# MCU.net
KiCad netlist of a schematic drawn in Altium Designer
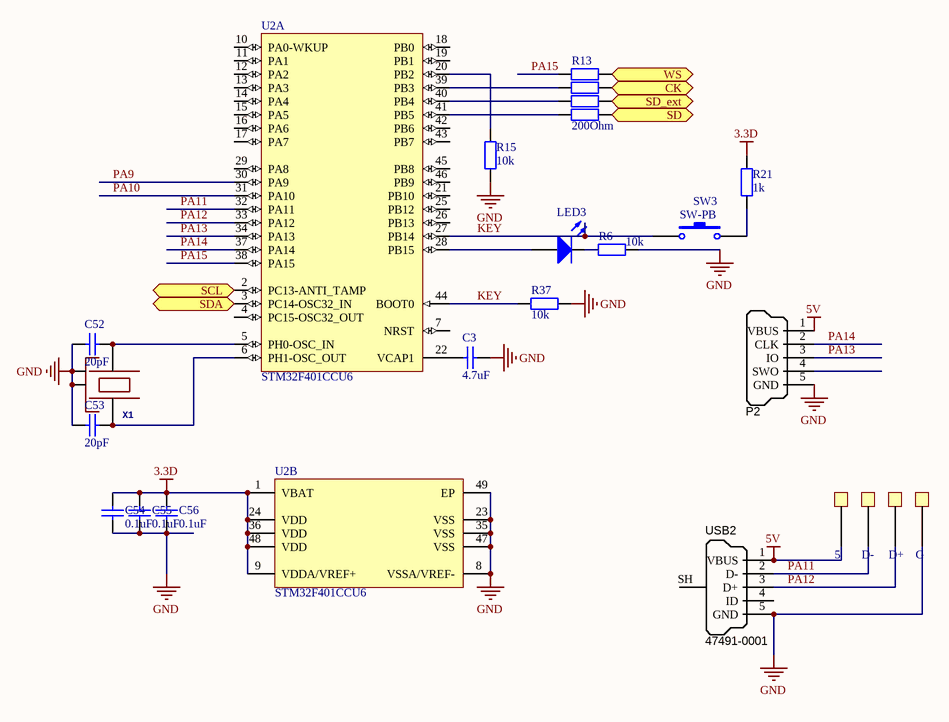
[diagram p0: MCU.SchDoc]

(export (version "E")
  (design (tool "Eeschema 10.0.6"))
  (components
    (comp (ref "5") (value "TestPad") (footprint "TestPad") (libsource (lib "sch") (part "TestPad")))
    (comp (ref "C3")
      (value "4.7uF")
      (footprint "0603L")
      (description "Capacitor")
      (fields (field (name "Comment") "Cap") (field (name "PUBLISHER") "Altium Limited"))
      (libsource (lib "RTC6705") (part "Cap"))
    )
    (comp (ref "C52")
      (value "20pF")
      (footprint "0402")
      (description "Capacitor")
      (fields (field (name "Comment") "Cap") (field (name "PUBLISHER") "Altium Limited"))
      (libsource (lib "RTC6705") (part "Cap"))
    )
    (comp (ref "C53")
      (value "20pF")
      (footprint "0402")
      (description "Capacitor")
      (fields (field (name "Comment") "Cap") (field (name "PUBLISHER") "Altium Limited"))
      (libsource (lib "RTC6705") (part "Cap"))
    )
    (comp (ref "C54")
      (value "0.1uF")
      (footprint "0402")
      (description "Capacitor")
      (fields (field (name "Comment") "Cap") (field (name "PUBLISHER") "Altium Limited"))
      (libsource (lib "RTC6705") (part "Cap"))
    )
    (comp (ref "C55")
      (value "0.1uF")
      (footprint "0402")
      (description "Capacitor")
      (fields (field (name "Comment") "Cap") (field (name "PUBLISHER") "Altium Limited"))
      (libsource (lib "RTC6705") (part "Cap"))
    )
    (comp (ref "C56")
      (value "0.1uF")
      (footprint "0402")
      (description "Capacitor")
      (fields (field (name "Comment") "Cap") (field (name "PUBLISHER") "Altium Limited"))
      (libsource (lib "RTC6705") (part "Cap"))
    )
    (comp (ref "D+") (value "TestPad") (footprint "TestPad") (libsource (lib "sch") (part "TestPad")))
    (comp (ref "D-") (value "TestPad") (footprint "TestPad") (libsource (lib "sch") (part "TestPad")))
    (comp (ref "G") (value "TestPad") (footprint "TestPad") (libsource (lib "sch") (part "TestPad")))
    (comp (ref "LED3")
      (value "LED0")
      (footprint "0603")
      (description "Typical INFRARED GaAs LED")
      (fields (field (name "PUBLISHER") "Altium Limited"))
      (libsource (lib "Miscellaneous Devices") (part "LED0"))
    )
    (comp (ref "P2")
      (value "SWD_MicroUSB")
      (footprint "MICRO-YZX")
      (description "Connector SMD USB Micro Type B middle mount")
      (libsource (lib "sch") (part "SWD_MicroUSB"))
    )
    (comp (ref "R6")
      (value "10k")
      (footprint "0402")
      (description "Resistor")
      (fields (field (name "PUBLISHER") "Altium Limited"))
      (libsource (lib "") (part "Res2_2"))
    )
    (comp (ref "R13")
      (value "200Ohm")
      (footprint "0402X4")
      (description "Resistor")
      (fields (field (name "Comment") "Res*4") (field (name "PUBLISHER") "Altium Limited"))
      (libsource (lib "sch") (part "Res*4"))
    )
    (comp (ref "R15")
      (value "10k")
      (footprint "0402")
      (description "Resistor")
      (fields (field (name "PUBLISHER") "Altium Limited"))
      (libsource (lib "") (part "Res2_1"))
    )
    (comp (ref "R21")
      (value "1k")
      (footprint "0402")
      (description "Resistor")
      (fields (field (name "PUBLISHER") "Altium Limited"))
      (libsource (lib "Miscellaneous Devices") (part "Res2"))
    )
    (comp (ref "R37")
      (value "10k")
      (footprint "0402")
      (description "Resistor")
      (fields (field (name "Comment") "Res2") (field (name "PUBLISHER") "Altium Limited"))
      (libsource (lib "RTC6705") (part "Res2"))
    )
    (comp (ref "SW3")
      (value "SW-PB")
      (footprint "SW3x4")
      (description "Switch")
      (fields (field (name "PUBLISHER") "Altium Limited"))
      (libsource (lib "Miscellaneous Devices") (part "SW-PB"))
    )
    (comp (ref "U2")
      (value "STM32F401CCU6")
      (footprint "STM-UFQFPN48_N")
      (fields (field (name "MANUFACTURER") "STMicroelectronics"))
      (libsource (lib "STMicroelectronics STM32 F4") (part "STM32F401CCU6"))
    )
    (comp (ref "USB2")
      (value "USB Micro Type B")
      (footprint "MICRO-YZX")
      (description "Connector SMD USB Micro Type B middle mount")
      (fields (field (name "MANUFACTURER PART NUMBER 1") "47491-0001"))
      (libsource (lib "PBL - Connectors") (part "USB_Micro_TypeB"))
    )
    (comp (ref "X1")
      (value "24.000 KHz 3.2x2.5mm 8-10pf")
      (footprint "OSCILLATOR-2.5x2.0")
      (description "Crystal Oscillator in 3.2x2.5 SMD")
      (libsource (lib "pixhawk2") (part "OSCILLATOR-3.2X2.5"))
    )
  )
  (nets
    (net (code "1") (name "/CK") (class "Default")
      (node (ref "R13") (pin "2") (pinfunction "2_2") (pintype "passive"))
    )
    (net (code "2") (name "/KEY") (class "Default")
      (node (ref "R37") (pin "1") (pinfunction "1_1") (pintype "passive"))
      (node (ref "SW3") (pin "1") (pinfunction "1_1") (pintype "passive"))
      (node (ref "U2") (pin "27") (pinfunction "PB14_27") (pintype "bidirectional"))
      (node (ref "U2") (pin "44") (pinfunction "BOOT0_44") (pintype "input"))
    )
    (net (code "3") (name "/PA9") (class "Default")
      (node (ref "U2") (pin "30") (pinfunction "PA9_30") (pintype "bidirectional"))
    )
    (net (code "4") (name "/PA10") (class "Default")
      (node (ref "U2") (pin "31") (pinfunction "PA10_31") (pintype "bidirectional"))
    )
    (net (code "5") (name "/PA11") (class "Default")
      (node (ref "D-") (pin "1") (pinfunction "3_1") (pintype "passive"))
      (node (ref "U2") (pin "32") (pinfunction "PA11_32") (pintype "bidirectional"))
      (node (ref "USB2") (pin "2") (pinfunction "D-_2") (pintype "passive"))
    )
    (net (code "6") (name "/PA12") (class "Default")
      (node (ref "D+") (pin "1") (pinfunction "3_1") (pintype "passive"))
      (node (ref "U2") (pin "33") (pinfunction "PA12_33") (pintype "bidirectional"))
      (node (ref "USB2") (pin "3") (pinfunction "D+_3") (pintype "passive"))
    )
    (net (code "7") (name "/PA13") (class "Default")
      (node (ref "P2") (pin "3") (pinfunction "IO_3") (pintype "passive"))
      (node (ref "U2") (pin "34") (pinfunction "PA13_34") (pintype "bidirectional"))
    )
    (net (code "8") (name "/PA14") (class "Default")
      (node (ref "P2") (pin "2") (pinfunction "CLK_2") (pintype "passive"))
      (node (ref "U2") (pin "37") (pinfunction "PA14_37") (pintype "bidirectional"))
    )
    (net (code "9") (name "/PA15") (class "Default")
      (node (ref "R13") (pin "8") (pinfunction "8_8") (pintype "passive"))
      (node (ref "U2") (pin "38") (pinfunction "PA15_38") (pintype "bidirectional"))
    )
    (net (code "10") (name "/SCL") (class "Default")
      (node (ref "U2") (pin "2") (pinfunction "PC13-ANTI_TAMP_2") (pintype "bidirectional"))
    )
    (net (code "11") (name "/SD") (class "Default")
      (node (ref "R13") (pin "4") (pinfunction "4_4") (pintype "passive"))
    )
    (net (code "12") (name "/SDA") (class "Default")
      (node (ref "U2") (pin "3") (pinfunction "PC14-OSC32_IN_3") (pintype "bidirectional"))
    )
    (net (code "13") (name "/SD_ext") (class "Default")
      (node (ref "R13") (pin "3") (pinfunction "3_3") (pintype "passive"))
    )
    (net (code "14") (name "/WS") (class "Default")
      (node (ref "R13") (pin "1") (pinfunction "1_1") (pintype "passive"))
    )
    (net (code "15") (name "3.3D") (class "Default")
      (node (ref "C54") (pin "2") (pinfunction "2_2") (pintype "passive"))
      (node (ref "C55") (pin "2") (pinfunction "2_2") (pintype "passive"))
      (node (ref "C56") (pin "2") (pinfunction "2_2") (pintype "passive"))
      (node (ref "R21") (pin "2") (pinfunction "2_2") (pintype "passive"))
      (node (ref "U2") (pin "1") (pinfunction "VBAT_1") (pintype "power_in"))
      (node (ref "U2") (pin "24") (pinfunction "VDD_24") (pintype "power_in"))
      (node (ref "U2") (pin "36") (pinfunction "VDD_36") (pintype "power_in"))
      (node (ref "U2") (pin "48") (pinfunction "VDD_48") (pintype "power_in"))
      (node (ref "U2") (pin "9") (pinfunction "VDDA/VREF+_9") (pintype "power_in"))
    )
    (net (code "16") (name "5V") (class "Default")
      (node (ref "5") (pin "1") (pinfunction "3_1") (pintype "passive"))
      (node (ref "P2") (pin "1") (pinfunction "VBUS_1") (pintype "passive"))
      (node (ref "USB2") (pin "1") (pinfunction "VBUS_1") (pintype "passive"))
    )
    (net (code "17") (name "GND") (class "Default")
      (node (ref "C3") (pin "1") (pinfunction "1_1") (pintype "passive"))
      (node (ref "C52") (pin "1") (pinfunction "1_1") (pintype "passive"))
      (node (ref "C53") (pin "1") (pinfunction "1_1") (pintype "passive"))
      (node (ref "C54") (pin "1") (pinfunction "1_1") (pintype "passive"))
      (node (ref "C55") (pin "1") (pinfunction "1_1") (pintype "passive"))
      (node (ref "C56") (pin "1") (pinfunction "1_1") (pintype "passive"))
      (node (ref "G") (pin "1") (pinfunction "3_1") (pintype "passive"))
      (node (ref "P2") (pin "5") (pinfunction "GND_5") (pintype "passive"))
      (node (ref "R15") (pin "2") (pinfunction "2_2") (pintype "passive"))
      (node (ref "R37") (pin "2") (pinfunction "2_2") (pintype "passive"))
      (node (ref "R6") (pin "2") (pinfunction "2_2") (pintype "passive"))
      (node (ref "U2") (pin "23") (pinfunction "VSS_23") (pintype "power_in"))
      (node (ref "U2") (pin "35") (pinfunction "VSS_35") (pintype "power_in"))
      (node (ref "U2") (pin "47") (pinfunction "VSS_47") (pintype "power_in"))
      (node (ref "U2") (pin "49") (pinfunction "EP_49") (pintype "power_in"))
      (node (ref "U2") (pin "8") (pinfunction "VSSA/VREF-_8") (pintype "power_in"))
      (node (ref "USB2") (pin "5") (pinfunction "GND_5") (pintype "passive"))
      (node (ref "X1") (pin "2") (pinfunction "NC_2_2") (pintype "open_emitter"))
      (node (ref "X1") (pin "4") (pinfunction "NC_4_4") (pintype "open_emitter"))
    )
    (net (code "18") (name "Net-(LED3-A)") (class "Default")
      (node (ref "LED3") (pin "1") (pinfunction "A_1") (pintype "passive"))
      (node (ref "U2") (pin "28") (pinfunction "PB15_28") (pintype "bidirectional"))
    )
    (net (code "19") (name "Net-(LED3-K)") (class "Default")
      (node (ref "LED3") (pin "2") (pinfunction "K_2") (pintype "passive"))
      (node (ref "R6") (pin "1") (pinfunction "1_1") (pintype "passive"))
    )
    (net (code "20") (name "Net-(R21-Pad1)") (class "Default")
      (node (ref "R21") (pin "1") (pinfunction "1_1") (pintype "passive"))
      (node (ref "SW3") (pin "2") (pinfunction "2_2") (pintype "passive"))
    )
    (net (code "21") (name "Net-(U2A-PB2)") (class "Default")
      (node (ref "R15") (pin "1") (pinfunction "1_1") (pintype "passive"))
      (node (ref "U2") (pin "20") (pinfunction "PB2_20") (pintype "bidirectional"))
    )
    (net (code "22") (name "Net-(U2A-PB3)") (class "Default")
      (node (ref "R13") (pin "7") (pinfunction "7_7") (pintype "passive"))
      (node (ref "U2") (pin "39") (pinfunction "PB3_39") (pintype "bidirectional"))
    )
    (net (code "23") (name "Net-(U2A-PB4)") (class "Default")
      (node (ref "R13") (pin "6") (pinfunction "6_6") (pintype "passive"))
      (node (ref "U2") (pin "40") (pinfunction "PB4_40") (pintype "bidirectional"))
    )
    (net (code "24") (name "Net-(U2A-PB5)") (class "Default")
      (node (ref "R13") (pin "5") (pinfunction "5_5") (pintype "passive"))
      (node (ref "U2") (pin "41") (pinfunction "PB5_41") (pintype "bidirectional"))
    )
    (net (code "25") (name "Net-(U2A-PH0-OSC_IN)") (class "Default")
      (node (ref "C52") (pin "2") (pinfunction "2_2") (pintype "passive"))
      (node (ref "U2") (pin "5") (pinfunction "PH0-OSC_IN_5") (pintype "bidirectional"))
      (node (ref "X1") (pin "1") (pinfunction "1_1") (pintype "passive"))
    )
    (net (code "26") (name "Net-(U2A-PH1-OSC_OUT)") (class "Default")
      (node (ref "C53") (pin "2") (pinfunction "2_2") (pintype "passive"))
      (node (ref "U2") (pin "6") (pinfunction "PH1-OSC_OUT_6") (pintype "bidirectional"))
      (node (ref "X1") (pin "3") (pinfunction "3_3") (pintype "passive"))
    )
    (net (code "27") (name "Net-(U2A-VCAP1)") (class "Default")
      (node (ref "C3") (pin "2") (pinfunction "2_2") (pintype "passive"))
      (node (ref "U2") (pin "22") (pinfunction "VCAP1_22") (pintype "power_in"))
    )
    (net (code "28") (name "unconnected-(P2-SWO-Pad4)") (class "Default")
      (node (ref "P2") (pin "4") (pinfunction "SWO_4") (pintype "passive"))
    )
    (net (code "29") (name "unconnected-(U2A-NRST-Pad7)") (class "Default")
      (node (ref "U2") (pin "7") (pinfunction "NRST_7") (pintype "bidirectional"))
    )
    (net (code "30") (name "unconnected-(U2A-PA0-WKUP-Pad10)") (class "Default")
      (node (ref "U2") (pin "10") (pinfunction "PA0-WKUP_10") (pintype "bidirectional"))
    )
    (net (code "31") (name "unconnected-(U2A-PA1-Pad11)") (class "Default")
      (node (ref "U2") (pin "11") (pinfunction "PA1_11") (pintype "bidirectional"))
    )
    (net (code "32") (name "unconnected-(U2A-PA2-Pad12)") (class "Default")
      (node (ref "U2") (pin "12") (pinfunction "PA2_12") (pintype "bidirectional"))
    )
    (net (code "33") (name "unconnected-(U2A-PA3-Pad13)") (class "Default")
      (node (ref "U2") (pin "13") (pinfunction "PA3_13") (pintype "bidirectional"))
    )
    (net (code "34") (name "unconnected-(U2A-PA4-Pad14)") (class "Default")
      (node (ref "U2") (pin "14") (pinfunction "PA4_14") (pintype "bidirectional"))
    )
    (net (code "35") (name "unconnected-(U2A-PA5-Pad15)") (class "Default")
      (node (ref "U2") (pin "15") (pinfunction "PA5_15") (pintype "bidirectional"))
    )
    (net (code "36") (name "unconnected-(U2A-PA6-Pad16)") (class "Default")
      (node (ref "U2") (pin "16") (pinfunction "PA6_16") (pintype "bidirectional"))
    )
    (net (code "37") (name "unconnected-(U2A-PA7-Pad17)") (class "Default")
      (node (ref "U2") (pin "17") (pinfunction "PA7_17") (pintype "bidirectional"))
    )
    (net (code "38") (name "unconnected-(U2A-PA8-Pad29)") (class "Default")
      (node (ref "U2") (pin "29") (pinfunction "PA8_29") (pintype "bidirectional"))
    )
    (net (code "39") (name "unconnected-(U2A-PB0-Pad18)") (class "Default")
      (node (ref "U2") (pin "18") (pinfunction "PB0_18") (pintype "bidirectional"))
    )
    (net (code "40") (name "unconnected-(U2A-PB1-Pad19)") (class "Default")
      (node (ref "U2") (pin "19") (pinfunction "PB1_19") (pintype "bidirectional"))
    )
    (net (code "41") (name "unconnected-(U2A-PB6-Pad42)") (class "Default")
      (node (ref "U2") (pin "42") (pinfunction "PB6_42") (pintype "bidirectional"))
    )
    (net (code "42") (name "unconnected-(U2A-PB7-Pad43)") (class "Default")
      (node (ref "U2") (pin "43") (pinfunction "PB7_43") (pintype "bidirectional"))
    )
    (net (code "43") (name "unconnected-(U2A-PB8-Pad45)") (class "Default")
      (node (ref "U2") (pin "45") (pinfunction "PB8_45") (pintype "bidirectional"))
    )
    (net (code "44") (name "unconnected-(U2A-PB9-Pad46)") (class "Default")
      (node (ref "U2") (pin "46") (pinfunction "PB9_46") (pintype "bidirectional"))
    )
    (net (code "45") (name "unconnected-(U2A-PB10-Pad21)") (class "Default")
      (node (ref "U2") (pin "21") (pinfunction "PB10_21") (pintype "bidirectional"))
    )
    (net (code "46") (name "unconnected-(U2A-PB12-Pad25)") (class "Default")
      (node (ref "U2") (pin "25") (pinfunction "PB12_25") (pintype "bidirectional"))
    )
    (net (code "47") (name "unconnected-(U2A-PB13-Pad26)") (class "Default")
      (node (ref "U2") (pin "26") (pinfunction "PB13_26") (pintype "bidirectional"))
    )
    (net (code "48") (name "unconnected-(U2A-PC15-OSC32_OUT-Pad4)") (class "Default")
      (node (ref "U2") (pin "4") (pinfunction "PC15-OSC32_OUT_4") (pintype "bidirectional"))
    )
    (net (code "49") (name "unconnected-(USB2-ID-Pad4)") (class "Default")
      (node (ref "USB2") (pin "4") (pinfunction "ID_4") (pintype "passive"))
    )
    (net (code "50") (name "unconnected-(USB2-Shell-PadSH)") (class "Default")
      (node (ref "USB2") (pin "SH") (pinfunction "Shell_SH") (pintype "passive"))
    )
  )
)
